# Arduino_Board_rev3.net
KiCad netlist of a schematic drawn in EAGLE
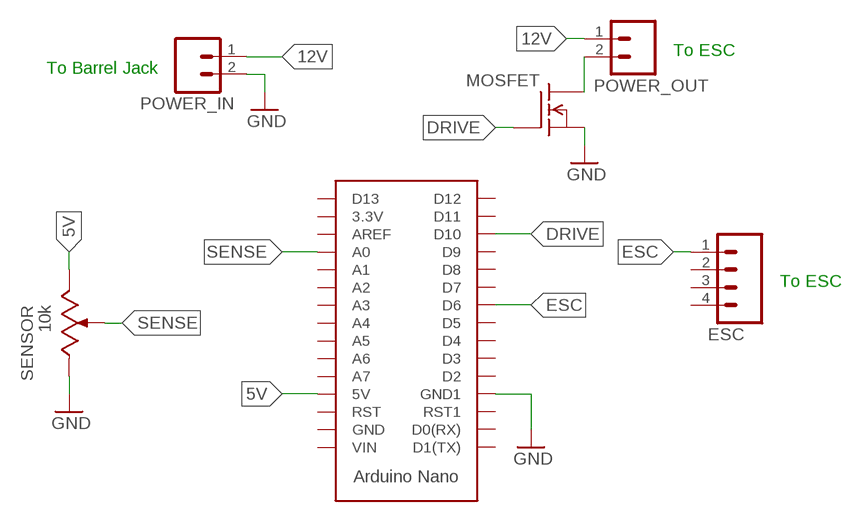
[diagram p0: schematic, sheet 1]

(export (version "E")
  (design (tool "Eeschema 10.0.6"))
  (components
    (comp (ref "ARDUINO_NANO")
      (value "ARDUINO_NANO")
      (footprint "eagle-import:ARDUINO_NANO")
      (libsource (lib "eagle-import") (part "ARDUINO_NANO"))
    )
    (comp (ref "ESC")
      (value "M04")
      (footprint "eagle-import:1X04")
      (libsource (lib "eagle-import") (part "M04"))
    )
    (comp (ref "MOSFET")
      (value "N-CHANNEL_MOSFETGENERIC")
      (footprint "eagle-import:TO-220-SINK")
      (libsource (lib "eagle-import") (part "N-CHANNEL_MOSFETGENERIC"))
    )
    (comp (ref "POWER_IN")
      (value "M02")
      (footprint "eagle-import:1X02")
      (libsource (lib "eagle-import") (part "M02"))
    )
    (comp (ref "POWER_OUT")
      (value "M02")
      (footprint "eagle-import:1X02")
      (libsource (lib "eagle-import") (part "M02"))
    )
    (comp (ref "SENSOR")
      (value "10k")
      (footprint "eagle-import:SV03A")
      (libsource (lib "eagle-import") (part "SV03"))
    )
  )
  (nets
    (net (code "1") (name "5V") (class "Default")
      (node (ref "ARDUINO_NANO") (pin "5V") (pinfunction "5V_5V") (pintype "bidirectional"))
      (node (ref "SENSOR") (pin "3") (pinfunction "A_3") (pintype "passive"))
    )
    (net (code "2") (name "12V") (class "Default")
      (node (ref "POWER_IN") (pin "1") (pinfunction "1_1") (pintype "passive"))
      (node (ref "POWER_OUT") (pin "1") (pinfunction "1_1") (pintype "passive"))
    )
    (net (code "3") (name "DRIVE") (class "Default")
      (node (ref "ARDUINO_NANO") (pin "D10") (pinfunction "D10_D10") (pintype "bidirectional"))
      (node (ref "MOSFET") (pin "1") (pinfunction "G_1") (pintype "passive"))
    )
    (net (code "4") (name "ESC") (class "Default")
      (node (ref "ARDUINO_NANO") (pin "D6") (pinfunction "D6_D6") (pintype "bidirectional"))
      (node (ref "ESC") (pin "1") (pinfunction "1_1") (pintype "passive"))
    )
    (net (code "5") (name "GND") (class "Default")
      (node (ref "ARDUINO_NANO") (pin "GND1") (pinfunction "GND1_GND1") (pintype "bidirectional"))
      (node (ref "MOSFET") (pin "3") (pinfunction "S_3") (pintype "passive"))
      (node (ref "POWER_IN") (pin "2") (pinfunction "2_2") (pintype "passive"))
      (node (ref "SENSOR") (pin "1") (pinfunction "E_1") (pintype "passive"))
    )
    (net (code "6") (name "Net-(MOSFET-D)") (class "Default")
      (node (ref "MOSFET") (pin "2") (pinfunction "D_2") (pintype "passive"))
      (node (ref "POWER_OUT") (pin "2") (pinfunction "2_2") (pintype "passive"))
    )
    (net (code "7") (name "SENSE") (class "Default")
      (node (ref "ARDUINO_NANO") (pin "A0") (pinfunction "A0_A0") (pintype "bidirectional"))
      (node (ref "SENSOR") (pin "2") (pinfunction "S_2") (pintype "passive"))
      (node (ref "SENSOR") (pin "2.1") (pinfunction "S_2.1") (pintype "passive"))
    )
    (net (code "8") (name "unconnected-(ARDUINO_NANO-Pad3.3V)") (class "Default")
      (node (ref "ARDUINO_NANO") (pin "3.3V") (pinfunction "3.3V_3.3V") (pintype "bidirectional"))
    )
    (net (code "9") (name "unconnected-(ARDUINO_NANO-PadA1)") (class "Default")
      (node (ref "ARDUINO_NANO") (pin "A1") (pinfunction "A1_A1") (pintype "bidirectional"))
    )
    (net (code "10") (name "unconnected-(ARDUINO_NANO-PadA2)") (class "Default")
      (node (ref "ARDUINO_NANO") (pin "A2") (pinfunction "A2_A2") (pintype "bidirectional"))
    )
    (net (code "11") (name "unconnected-(ARDUINO_NANO-PadA3)") (class "Default")
      (node (ref "ARDUINO_NANO") (pin "A3") (pinfunction "A3_A3") (pintype "bidirectional"))
    )
    (net (code "12") (name "unconnected-(ARDUINO_NANO-PadA4)") (class "Default")
      (node (ref "ARDUINO_NANO") (pin "A4") (pinfunction "A4_A4") (pintype "bidirectional"))
    )
    (net (code "13") (name "unconnected-(ARDUINO_NANO-PadA5)") (class "Default")
      (node (ref "ARDUINO_NANO") (pin "A5") (pinfunction "A5_A5") (pintype "bidirectional"))
    )
    (net (code "14") (name "unconnected-(ARDUINO_NANO-PadA6)") (class "Default")
      (node (ref "ARDUINO_NANO") (pin "A6") (pinfunction "A6_A6") (pintype "bidirectional"))
    )
    (net (code "15") (name "unconnected-(ARDUINO_NANO-PadA7)") (class "Default")
      (node (ref "ARDUINO_NANO") (pin "A7") (pinfunction "A7_A7") (pintype "bidirectional"))
    )
    (net (code "16") (name "unconnected-(ARDUINO_NANO-PadAREF)") (class "Default")
      (node (ref "ARDUINO_NANO") (pin "AREF") (pinfunction "AREF_AREF") (pintype "bidirectional"))
    )
    (net (code "17") (name "unconnected-(ARDUINO_NANO-PadD0(RX))") (class "Default")
      (node (ref "ARDUINO_NANO") (pin "D0(RX)") (pinfunction "D0(RX)_D0(RX)") (pintype "bidirectional"))
    )
    (net (code "18") (name "unconnected-(ARDUINO_NANO-PadD1(TX))") (class "Default")
      (node (ref "ARDUINO_NANO") (pin "D1(TX)") (pinfunction "D1(TX)_D1(TX)") (pintype "bidirectional"))
    )
    (net (code "19") (name "unconnected-(ARDUINO_NANO-PadD2)") (class "Default")
      (node (ref "ARDUINO_NANO") (pin "D2") (pinfunction "D2_D2") (pintype "bidirectional"))
    )
    (net (code "20") (name "unconnected-(ARDUINO_NANO-PadD3)") (class "Default")
      (node (ref "ARDUINO_NANO") (pin "D3") (pinfunction "D3_D3") (pintype "bidirectional"))
    )
    (net (code "21") (name "unconnected-(ARDUINO_NANO-PadD4)") (class "Default")
      (node (ref "ARDUINO_NANO") (pin "D4") (pinfunction "D4_D4") (pintype "bidirectional"))
    )
    (net (code "22") (name "unconnected-(ARDUINO_NANO-PadD5)") (class "Default")
      (node (ref "ARDUINO_NANO") (pin "D5") (pinfunction "D5_D5") (pintype "bidirectional"))
    )
    (net (code "23") (name "unconnected-(ARDUINO_NANO-PadD7)") (class "Default")
      (node (ref "ARDUINO_NANO") (pin "D7") (pinfunction "D7_D7") (pintype "bidirectional"))
    )
    (net (code "24") (name "unconnected-(ARDUINO_NANO-PadD8)") (class "Default")
      (node (ref "ARDUINO_NANO") (pin "D8") (pinfunction "D8_D8") (pintype "bidirectional"))
    )
    (net (code "25") (name "unconnected-(ARDUINO_NANO-PadD9)") (class "Default")
      (node (ref "ARDUINO_NANO") (pin "D9") (pinfunction "D9_D9") (pintype "bidirectional"))
    )
    (net (code "26") (name "unconnected-(ARDUINO_NANO-PadD11)") (class "Default")
      (node (ref "ARDUINO_NANO") (pin "D11") (pinfunction "D11_D11") (pintype "bidirectional"))
    )
    (net (code "27") (name "unconnected-(ARDUINO_NANO-PadD12)") (class "Default")
      (node (ref "ARDUINO_NANO") (pin "D12") (pinfunction "D12_D12") (pintype "bidirectional"))
    )
    (net (code "28") (name "unconnected-(ARDUINO_NANO-PadD13)") (class "Default")
      (node (ref "ARDUINO_NANO") (pin "D13") (pinfunction "D13_D13") (pintype "bidirectional"))
    )
    (net (code "29") (name "unconnected-(ARDUINO_NANO-PadGND)") (class "Default")
      (node (ref "ARDUINO_NANO") (pin "GND") (pinfunction "GND_GND") (pintype "bidirectional"))
    )
    (net (code "30") (name "unconnected-(ARDUINO_NANO-PadRST)") (class "Default")
      (node (ref "ARDUINO_NANO") (pin "RST") (pinfunction "RST_RST") (pintype "bidirectional"))
    )
    (net (code "31") (name "unconnected-(ARDUINO_NANO-PadRST1)") (class "Default")
      (node (ref "ARDUINO_NANO") (pin "RST1") (pinfunction "RST1_RST1") (pintype "bidirectional"))
    )
    (net (code "32") (name "unconnected-(ARDUINO_NANO-PadVIN)") (class "Default")
      (node (ref "ARDUINO_NANO") (pin "VIN") (pinfunction "VIN_VIN") (pintype "bidirectional"))
    )
    (net (code "33") (name "unconnected-(ESC-Pad2)") (class "Default")
      (node (ref "ESC") (pin "2") (pinfunction "2_2") (pintype "passive"))
    )
    (net (code "34") (name "unconnected-(ESC-Pad3)") (class "Default")
      (node (ref "ESC") (pin "3") (pinfunction "3_3") (pintype "passive"))
    )
    (net (code "35") (name "unconnected-(ESC-Pad4)") (class "Default")
      (node (ref "ESC") (pin "4") (pinfunction "4_4") (pintype "passive"))
    )
  )
)
